# timetracker-1-8-rendered.net
KiCad netlist of a schematic drawn in EAGLE
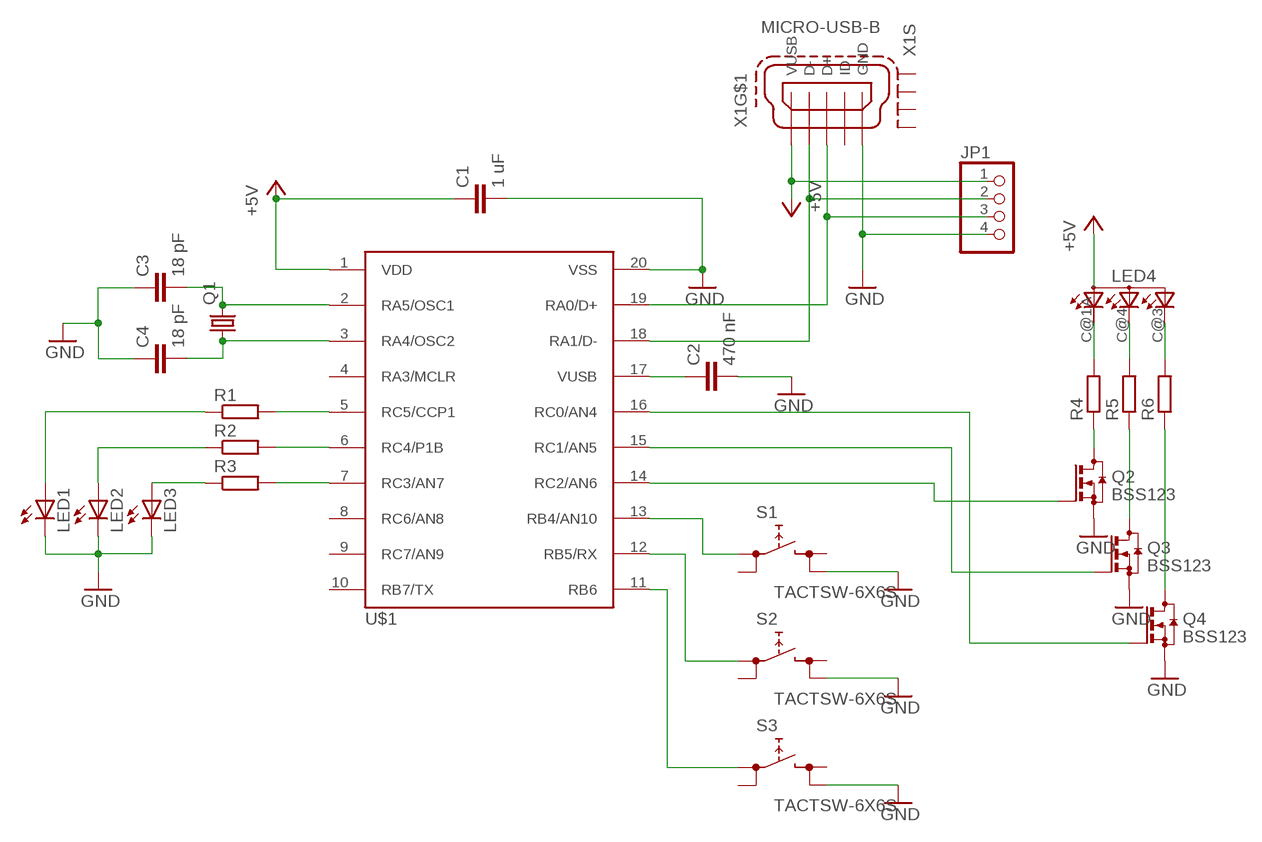
[diagram p0: schematic, sheet 1]

(export (version "E")
  (design (tool "Eeschema 10.0.6"))
  (components
    (comp (ref "C1")
      (value "1 uF")
      (footprint "eagle-import:C0805")
      (libsource (lib "eagle-import") (part "C-EUC0805"))
    )
    (comp (ref "C2")
      (value "470 nF")
      (footprint "eagle-import:C0805")
      (libsource (lib "eagle-import") (part "C-EUC0805"))
    )
    (comp (ref "C3")
      (value "18 pF")
      (footprint "eagle-import:C0805")
      (libsource (lib "eagle-import") (part "C-EUC0805"))
    )
    (comp (ref "C4")
      (value "18 pF")
      (footprint "eagle-import:C0805")
      (libsource (lib "eagle-import") (part "C-EUC0805"))
    )
    (comp (ref "JP1")
      (value "PINHD-1X4")
      (footprint "eagle-import:1X04")
      (libsource (lib "eagle-import") (part "PINHD-1X4"))
    )
    (comp (ref "LED1")
      (value "LEDSML0805")
      (footprint "eagle-import:SML0805")
      (libsource (lib "eagle-import") (part "LEDSML0805"))
    )
    (comp (ref "LED2")
      (value "LEDSML0805")
      (footprint "eagle-import:SML0805")
      (libsource (lib "eagle-import") (part "LEDSML0805"))
    )
    (comp (ref "LED3")
      (value "LEDSML0805")
      (footprint "eagle-import:SML0805")
      (libsource (lib "eagle-import") (part "LEDSML0805"))
    )
    (comp (ref "LED4")
      (value "RGBLED-3P-LCC-4")
      (footprint "eagle-import:P-LCC-4")
      (libsource (lib "eagle-import") (part "RGBLED-3P-LCC-4"))
    )
    (comp (ref "Q1")
      (value "CRYSTALHC49UP")
      (footprint "eagle-import:HC49UP")
      (libsource (lib "eagle-import") (part "CRYSTALHC49UP"))
    )
    (comp (ref "Q2")
      (value "BSS123")
      (footprint "eagle-import:SOT23")
      (libsource (lib "eagle-import") (part "BSS123"))
    )
    (comp (ref "Q3")
      (value "BSS123")
      (footprint "eagle-import:SOT23")
      (libsource (lib "eagle-import") (part "BSS123"))
    )
    (comp (ref "Q4")
      (value "BSS123")
      (footprint "eagle-import:SOT23")
      (libsource (lib "eagle-import") (part "BSS123"))
    )
    (comp (ref "R1")
      (value "R-EU_R0805")
      (footprint "eagle-import:R0805")
      (libsource (lib "eagle-import") (part "R-EU_R0805"))
    )
    (comp (ref "R2")
      (value "R-EU_R0805")
      (footprint "eagle-import:R0805")
      (libsource (lib "eagle-import") (part "R-EU_R0805"))
    )
    (comp (ref "R3")
      (value "R-EU_R0805")
      (footprint "eagle-import:R0805")
      (libsource (lib "eagle-import") (part "R-EU_R0805"))
    )
    (comp (ref "R4")
      (value "R-EU_R0805")
      (footprint "eagle-import:R0805")
      (libsource (lib "eagle-import") (part "R-EU_R0805"))
    )
    (comp (ref "R5")
      (value "R-EU_R0805")
      (footprint "eagle-import:R0805")
      (libsource (lib "eagle-import") (part "R-EU_R0805"))
    )
    (comp (ref "R6")
      (value "R-EU_R0805")
      (footprint "eagle-import:R0805")
      (libsource (lib "eagle-import") (part "R-EU_R0805"))
    )
    (comp (ref "S1")
      (value "TACTSW-6X6S")
      (footprint "eagle-import:TACTSW-6X6")
      (libsource (lib "eagle-import") (part "TACTSW-6X6S"))
    )
    (comp (ref "S2")
      (value "TACTSW-6X6S")
      (footprint "eagle-import:TACTSW-6X6")
      (libsource (lib "eagle-import") (part "TACTSW-6X6S"))
    )
    (comp (ref "S3")
      (value "TACTSW-6X6S")
      (footprint "eagle-import:TACTSW-6X6")
      (libsource (lib "eagle-import") (part "TACTSW-6X6S"))
    )
    (comp (ref "U$1")
      (value "PIC18F14K50SMD")
      (footprint "eagle-import:DIL20-SMD")
      (libsource (lib "eagle-import") (part "PIC18F14K50SMD"))
    )
    (comp (ref "X1")
      (value "MICRO-USB-B")
      (footprint "eagle-import:MICRO-B-PAC")
      (libsource (lib "eagle-import") (part "MICRO-USB-B"))
    )
  )
  (nets
    (net (code "1") (name "+5V") (class "Default")
      (node (ref "C1") (pin "1") (pinfunction "1_1") (pintype "passive"))
      (node (ref "JP1") (pin "1") (pinfunction "1_1") (pintype "passive"))
      (node (ref "LED4") (pin "A") (pinfunction "A2_A") (pintype "passive"))
      (node (ref "U$1") (pin "1") (pinfunction "VDD_1") (pintype "bidirectional"))
      (node (ref "X1") (pin "1") (pinfunction "VUSB_1") (pintype "passive"))
    )
    (net (code "2") (name "GND") (class "Default")
      (node (ref "C1") (pin "2") (pinfunction "2_2") (pintype "passive"))
      (node (ref "C2") (pin "2") (pinfunction "2_2") (pintype "passive"))
      (node (ref "C3") (pin "1") (pinfunction "1_1") (pintype "passive"))
      (node (ref "C4") (pin "1") (pinfunction "1_1") (pintype "passive"))
      (node (ref "JP1") (pin "4") (pinfunction "4_4") (pintype "passive"))
      (node (ref "LED1") (pin "C") (pinfunction "C_C") (pintype "passive"))
      (node (ref "LED2") (pin "C") (pinfunction "C_C") (pintype "passive"))
      (node (ref "LED3") (pin "C") (pinfunction "C_C") (pintype "passive"))
      (node (ref "Q2") (pin "2") (pinfunction "S_2") (pintype "passive"))
      (node (ref "Q3") (pin "2") (pinfunction "S_2") (pintype "passive"))
      (node (ref "Q4") (pin "2") (pinfunction "S_2") (pintype "passive"))
      (node (ref "S1") (pin "4") (pinfunction "2.2_4") (pintype "passive"))
      (node (ref "S2") (pin "4") (pinfunction "2.2_4") (pintype "passive"))
      (node (ref "S3") (pin "4") (pinfunction "2.2_4") (pintype "passive"))
      (node (ref "U$1") (pin "20") (pinfunction "VSS_20") (pintype "bidirectional"))
      (node (ref "X1") (pin "5") (pinfunction "GND_5") (pintype "passive"))
    )
    (net (code "3") (name "Net-(LED1-PadA)") (class "Default")
      (node (ref "LED1") (pin "A") (pinfunction "A_A") (pintype "passive"))
      (node (ref "R1") (pin "1") (pinfunction "1_1") (pintype "passive"))
    )
    (net (code "4") (name "Net-(LED2-PadA)") (class "Default")
      (node (ref "LED2") (pin "A") (pinfunction "A_A") (pintype "passive"))
      (node (ref "R2") (pin "1") (pinfunction "1_1") (pintype "passive"))
    )
    (net (code "5") (name "Net-(LED3-PadA)") (class "Default")
      (node (ref "LED3") (pin "A") (pinfunction "A_A") (pintype "passive"))
      (node (ref "R3") (pin "1") (pinfunction "1_1") (pintype "passive"))
    )
    (net (code "6") (name "Net-(LED4-CBLUE)") (class "Default")
      (node (ref "LED4") (pin "C@3") (pinfunction "CBLUE_C@3") (pintype "passive"))
      (node (ref "R6") (pin "2") (pinfunction "2_2") (pintype "passive"))
    )
    (net (code "7") (name "Net-(LED4-CGREEN)") (class "Default")
      (node (ref "LED4") (pin "C@4") (pinfunction "CGREEN_C@4") (pintype "passive"))
      (node (ref "R5") (pin "2") (pinfunction "2_2") (pintype "passive"))
    )
    (net (code "8") (name "Net-(LED4-CRED)") (class "Default")
      (node (ref "LED4") (pin "C@1") (pinfunction "CRED_C@1") (pintype "passive"))
      (node (ref "R4") (pin "2") (pinfunction "2_2") (pintype "passive"))
    )
    (net (code "9") (name "Net-(Q2-D)") (class "Default")
      (node (ref "Q2") (pin "3") (pinfunction "D_3") (pintype "passive"))
      (node (ref "R4") (pin "1") (pinfunction "1_1") (pintype "passive"))
    )
    (net (code "10") (name "Net-(Q2-G)") (class "Default")
      (node (ref "Q2") (pin "1") (pinfunction "G_1") (pintype "passive"))
      (node (ref "U$1") (pin "14") (pinfunction "RC2/AN6_14") (pintype "bidirectional"))
    )
    (net (code "11") (name "Net-(Q3-D)") (class "Default")
      (node (ref "Q3") (pin "3") (pinfunction "D_3") (pintype "passive"))
      (node (ref "R5") (pin "1") (pinfunction "1_1") (pintype "passive"))
    )
    (net (code "12") (name "Net-(Q3-G)") (class "Default")
      (node (ref "Q3") (pin "1") (pinfunction "G_1") (pintype "passive"))
      (node (ref "U$1") (pin "15") (pinfunction "RC1/AN5_15") (pintype "bidirectional"))
    )
    (net (code "13") (name "Net-(Q4-D)") (class "Default")
      (node (ref "Q4") (pin "3") (pinfunction "D_3") (pintype "passive"))
      (node (ref "R6") (pin "1") (pinfunction "1_1") (pintype "passive"))
    )
    (net (code "14") (name "Net-(Q4-G)") (class "Default")
      (node (ref "Q4") (pin "1") (pinfunction "G_1") (pintype "passive"))
      (node (ref "U$1") (pin "16") (pinfunction "RC0/AN4_16") (pintype "bidirectional"))
    )
    (net (code "15") (name "Net-(S1-1.1)") (class "Default")
      (node (ref "S1") (pin "1") (pinfunction "1.1_1") (pintype "passive"))
      (node (ref "U$1") (pin "13") (pinfunction "RB4/AN10_13") (pintype "bidirectional"))
    )
    (net (code "16") (name "Net-(S2-1.1)") (class "Default")
      (node (ref "S2") (pin "1") (pinfunction "1.1_1") (pintype "passive"))
      (node (ref "U$1") (pin "12") (pinfunction "RB5/RX_12") (pintype "bidirectional"))
    )
    (net (code "17") (name "Net-(S3-1.1)") (class "Default")
      (node (ref "S3") (pin "1") (pinfunction "1.1_1") (pintype "passive"))
      (node (ref "U$1") (pin "11") (pinfunction "RB6_11") (pintype "bidirectional"))
    )
    (net (code "18") (name "Net-(U$1-RA0{slash}D+)") (class "Default")
      (node (ref "JP1") (pin "3") (pinfunction "3_3") (pintype "passive"))
      (node (ref "U$1") (pin "19") (pinfunction "RA0/D+_19") (pintype "bidirectional"))
      (node (ref "X1") (pin "3") (pinfunction "D+_3") (pintype "passive"))
    )
    (net (code "19") (name "Net-(U$1-RA1{slash}D-)") (class "Default")
      (node (ref "JP1") (pin "2") (pinfunction "2_2") (pintype "passive"))
      (node (ref "U$1") (pin "18") (pinfunction "RA1/D-_18") (pintype "bidirectional"))
      (node (ref "X1") (pin "2") (pinfunction "D-_2") (pintype "passive"))
    )
    (net (code "20") (name "Net-(U$1-RA4{slash}OSC2)") (class "Default")
      (node (ref "C4") (pin "2") (pinfunction "2_2") (pintype "passive"))
      (node (ref "Q1") (pin "1") (pinfunction "1_1") (pintype "passive"))
      (node (ref "U$1") (pin "3") (pinfunction "RA4/OSC2_3") (pintype "bidirectional"))
    )
    (net (code "21") (name "Net-(U$1-RA5{slash}OSC1)") (class "Default")
      (node (ref "C3") (pin "2") (pinfunction "2_2") (pintype "passive"))
      (node (ref "Q1") (pin "2") (pinfunction "2_2") (pintype "passive"))
      (node (ref "U$1") (pin "2") (pinfunction "RA5/OSC1_2") (pintype "bidirectional"))
    )
    (net (code "22") (name "Net-(U$1-RC3{slash}AN7)") (class "Default")
      (node (ref "R3") (pin "2") (pinfunction "2_2") (pintype "passive"))
      (node (ref "U$1") (pin "7") (pinfunction "RC3/AN7_7") (pintype "bidirectional"))
    )
    (net (code "23") (name "Net-(U$1-RC4{slash}P1B)") (class "Default")
      (node (ref "R2") (pin "2") (pinfunction "2_2") (pintype "passive"))
      (node (ref "U$1") (pin "6") (pinfunction "RC4/P1B_6") (pintype "bidirectional"))
    )
    (net (code "24") (name "Net-(U$1-RC5{slash}CCP1)") (class "Default")
      (node (ref "R1") (pin "2") (pinfunction "2_2") (pintype "passive"))
      (node (ref "U$1") (pin "5") (pinfunction "RC5/CCP1_5") (pintype "bidirectional"))
    )
    (net (code "25") (name "Net-(U$1-VUSB)") (class "Default")
      (node (ref "C2") (pin "1") (pinfunction "1_1") (pintype "passive"))
      (node (ref "U$1") (pin "17") (pinfunction "VUSB_17") (pintype "bidirectional"))
    )
    (net (code "26") (name "unconnected-(S1-1.2-Pad2)") (class "Default")
      (node (ref "S1") (pin "2") (pinfunction "1.2_2") (pintype "passive"))
    )
    (net (code "27") (name "unconnected-(S1-2.1-Pad3)") (class "Default")
      (node (ref "S1") (pin "3") (pinfunction "2.1_3") (pintype "passive"))
    )
    (net (code "28") (name "unconnected-(S2-1.2-Pad2)") (class "Default")
      (node (ref "S2") (pin "2") (pinfunction "1.2_2") (pintype "passive"))
    )
    (net (code "29") (name "unconnected-(S2-2.1-Pad3)") (class "Default")
      (node (ref "S2") (pin "3") (pinfunction "2.1_3") (pintype "passive"))
    )
    (net (code "30") (name "unconnected-(S3-1.2-Pad2)") (class "Default")
      (node (ref "S3") (pin "2") (pinfunction "1.2_2") (pintype "passive"))
    )
    (net (code "31") (name "unconnected-(S3-2.1-Pad3)") (class "Default")
      (node (ref "S3") (pin "3") (pinfunction "2.1_3") (pintype "passive"))
    )
    (net (code "32") (name "unconnected-(U$1-RA3{slash}MCLR-Pad4)") (class "Default")
      (node (ref "U$1") (pin "4") (pinfunction "RA3/MCLR_4") (pintype "bidirectional"))
    )
    (net (code "33") (name "unconnected-(U$1-RB7{slash}TX-Pad10)") (class "Default")
      (node (ref "U$1") (pin "10") (pinfunction "RB7/TX_10") (pintype "bidirectional"))
    )
    (net (code "34") (name "unconnected-(U$1-RC6{slash}AN8-Pad8)") (class "Default")
      (node (ref "U$1") (pin "8") (pinfunction "RC6/AN8_8") (pintype "bidirectional"))
    )
    (net (code "35") (name "unconnected-(U$1-RC7{slash}AN9-Pad9)") (class "Default")
      (node (ref "U$1") (pin "9") (pinfunction "RC7/AN9_9") (pintype "bidirectional"))
    )
    (net (code "36") (name "unconnected-(X1A-ID-Pad4)") (class "Default")
      (node (ref "X1") (pin "4") (pinfunction "ID_4") (pintype "passive"))
    )
    (net (code "37") (name "unconnected-(X1B-S1-PadM1)") (class "Default")
      (node (ref "X1") (pin "M1") (pinfunction "S1_M1") (pintype "passive"))
    )
    (net (code "38") (name "unconnected-(X1B-S2-PadM2)") (class "Default")
      (node (ref "X1") (pin "M2") (pinfunction "S2_M2") (pintype "passive"))
    )
    (net (code "39") (name "unconnected-(X1B-S3-PadM3)") (class "Default")
      (node (ref "X1") (pin "M3") (pinfunction "S3_M3") (pintype "passive"))
    )
    (net (code "40") (name "unconnected-(X1B-S4-PadM4)") (class "Default")
      (node (ref "X1") (pin "M4") (pinfunction "S4_M4") (pintype "passive"))
    )
  )
)
